# LVDS.net
KiCad netlist of a schematic drawn in Altium Designer
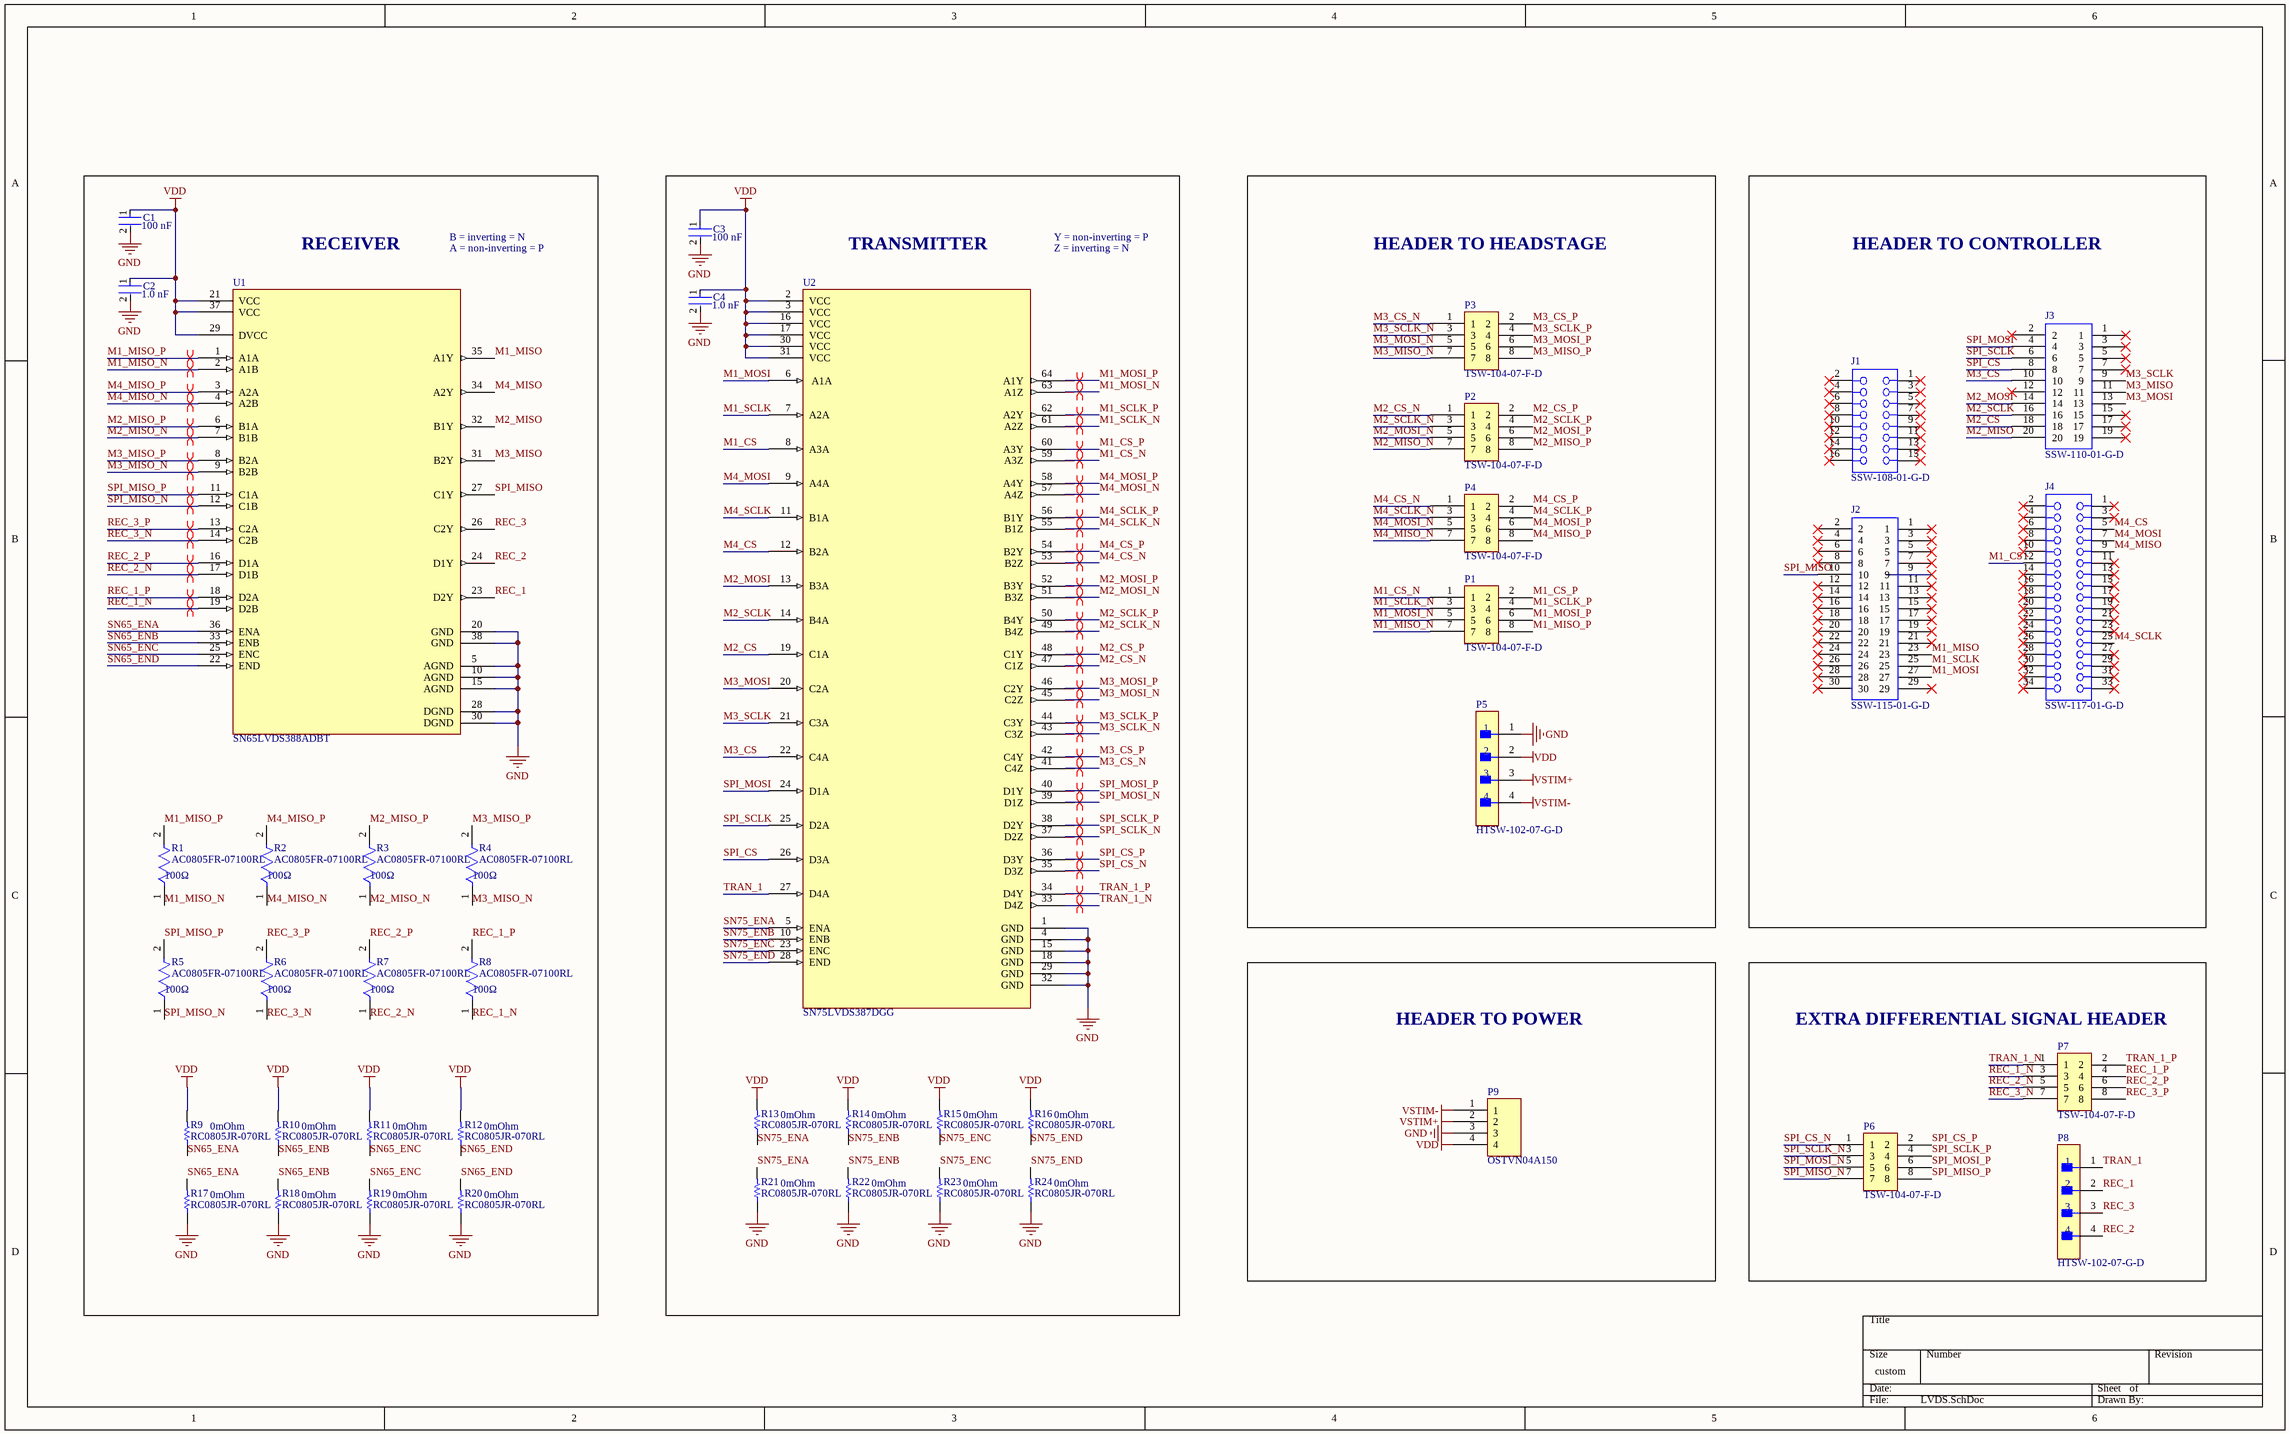
[diagram p0: LVDS.SchDoc]

(export (version "E")
  (design (tool "Eeschema 10.0.6"))
  (components
    (comp (ref "C1")
      (value "CC0805MRX7R9BB104")
      (footprint "FP-CC0805-0_85-MFG")
      (description "CAP CER 0.1UF 50V X7R 0805")
      (fields
        (field (name "TOLERANCE") "0.2")
        (field (name "OCTOPART") "https://octopart.com/cc0805mrx7r9bb104-yageo-30261726")
        (field (name "CAPACITANCE") "100 nF")
      )
      (libsource (lib "Altium Content Vault") (part "11868f565c42a9108669ba33697ecf6"))
    )
    (comp (ref "C2")
      (value "CC0805KRX7R9BB102")
      (footprint "FP-CC0805-0_85-MFG")
      (description "CAP CER 1000PF 50V X7R 0805")
      (fields
        (field (name "MANUFACTURER") "Yageo")
        (field (name "OCTOPART") "https://octopart.com/cc0805krx7r9bb102-yageo-39467744")
        (field (name "CAPACITANCE") "1.0 nF")
      )
      (libsource (lib "Altium Content Vault") (part "11868f565c42a9108669ba33697ecf6"))
    )
    (comp (ref "C3")
      (value "CC0805MRX7R9BB104")
      (footprint "FP-CC0805-0_85-MFG")
      (description "CAP CER 0.1UF 50V X7R 0805")
      (fields
        (field (name "TOLERANCE") "0.2")
        (field (name "OCTOPART") "https://octopart.com/cc0805mrx7r9bb104-yageo-30261726")
        (field (name "CAPACITANCE") "100 nF")
      )
      (libsource (lib "Altium Content Vault") (part "11868f565c42a9108669ba33697ecf6"))
    )
    (comp (ref "C4")
      (value "CC0805KRX7R9BB102")
      (footprint "FP-CC0805-0_85-MFG")
      (description "CAP CER 1000PF 50V X7R 0805")
      (fields
        (field (name "MANUFACTURER") "Yageo")
        (field (name "OCTOPART") "https://octopart.com/cc0805krx7r9bb102-yageo-39467744")
        (field (name "CAPACITANCE") "1.0 nF")
      )
      (libsource (lib "Altium Content Vault") (part "11868f565c42a9108669ba33697ecf6"))
    )
    (comp (ref "J1")
      (value "SSW-108-01-G-D")
      (footprint "SMTC-SSW-108-01-X-D")
      (description "SQ Post Socket, Through-hole, Vertical, -55 to 125 degC, 2.54mm Pitch, 16-Pin, Female, RoHS")
      (fields (field (name "MANUFACTURER") "Samtec"))
      (libsource (lib "Altium Content Vault") (part "SMTC-SSW-108-X-X-D-X"))
    )
    (comp (ref "J2")
      (value "SSW-115-01-G-D")
      (footprint "SAMTEC_SSW-115-01-G-D")
      (fields (field (name "MANUFACTURER") "Samtec"))
      (libsource (lib "LVDS") (part "SSW-115-01-G-D"))
    )
    (comp (ref "J3")
      (value "SSW-110-01-G-D")
      (footprint "SAMTEC_SSW-110-01-G-D")
      (fields (field (name "MANUFACTURER") "Samtec"))
      (libsource (lib "LVDS") (part "SSW-110-01-G-D"))
    )
    (comp (ref "J4")
      (value "SSW-117-01-G-D")
      (footprint "SMTC-SSW-117-01-X-D")
      (description "SQ Post Socket, Through-hole, Vertical, -55 to 125 degC, 2.54 mm Pitch, 34-Pin, Female, RoHS")
      (fields (field (name "MANUFACTURER") "Samtec"))
      (libsource (lib "Altium Content Vault") (part "SMTC-SSW-117-01-X-D"))
    )
    (comp (ref "P1")
      (value "TSW-104-07-F-D")
      (footprint "SAMTEC_TSW-104-07-F-D")
      (fields (field (name "MANUFACTURER") "Samtec"))
      (libsource (lib "LVDS") (part "TSW-104-07-F-D"))
    )
    (comp (ref "P2")
      (value "TSW-104-07-F-D")
      (footprint "SAMTEC_TSW-104-07-F-D")
      (fields (field (name "MANUFACTURER") "Samtec"))
      (libsource (lib "LVDS") (part "TSW-104-07-F-D"))
    )
    (comp (ref "P3")
      (value "TSW-104-07-F-D")
      (footprint "SAMTEC_TSW-104-07-F-D")
      (fields (field (name "MANUFACTURER") "Samtec"))
      (libsource (lib "LVDS") (part "TSW-104-07-F-D"))
    )
    (comp (ref "P4")
      (value "TSW-104-07-F-D")
      (footprint "SAMTEC_TSW-104-07-F-D")
      (fields (field (name "MANUFACTURER") "Samtec"))
      (libsource (lib "LVDS") (part "TSW-104-07-F-D"))
    )
    (comp (ref "P5")
      (value "HTSW-102-07-G-D")
      (footprint "FP-HTSW-102-07-G-D-MFG")
      (description "CONN HEADER VERT 4POS 2.54MM")
      (fields
        (field (name "MANUFACTURER") "Samtec")
        (field (name "OCTOPART") "https://octopart.com/htsw-102-07-g-d-samtec-10531767")
      )
      (libsource (lib "Altium Content Vault") (part "299a8cea1bdcbc3624fe62c390fa72c"))
    )
    (comp (ref "P6")
      (value "TSW-104-07-F-D")
      (footprint "SAMTEC_TSW-104-07-F-D")
      (fields (field (name "MANUFACTURER") "Samtec"))
      (libsource (lib "LVDS") (part "TSW-104-07-F-D"))
    )
    (comp (ref "P7")
      (value "TSW-104-07-F-D")
      (footprint "SAMTEC_TSW-104-07-F-D")
      (fields (field (name "MANUFACTURER") "Samtec"))
      (libsource (lib "LVDS") (part "TSW-104-07-F-D"))
    )
    (comp (ref "P8")
      (value "HTSW-102-07-G-D")
      (footprint "FP-HTSW-102-07-G-D-MFG")
      (description "CONN HEADER VERT 4POS 2.54MM")
      (fields
        (field (name "MANUFACTURER") "Samtec")
        (field (name "OCTOPART") "https://octopart.com/htsw-102-07-g-d-samtec-10531767")
      )
      (libsource (lib "Altium Content Vault") (part "299a8cea1bdcbc3624fe62c390fa72c"))
    )
    (comp (ref "P9")
      (value "OSTVN04A150")
      (footprint "OSTVN04A150")
      (description "Barrier Strip Terminal Block, 6A, 1 Row(s), 1 Deck(s)")
      (fields (field (name "MANUFACTURER") "On-Shore Technology") (field (name "SAFETY APPROVAL") "UL,CUL"))
      (libsource (lib "LVDS") (part "OSTVN04A150"))
    )
    (comp (ref "R1")
      (value "AC0805FR-07100RL")
      (footprint "FP-AC0805-MFG")
      (description "Res Thick Film 0805 100 Ohm 1% 1/8W ±100ppm/°C Molded SMD Paper T/R")
      (fields
        (field (name "TOLERANCE") "0.01")
        (field (name "OCTOPART") "https://octopart.com/ac0805fr-07100rl-yageo-24517276")
        (field (name "RESISTANCE") "100Ω")
      )
      (libsource (lib "Altium Content Vault") (part "1029c3af85768c4190bb7ad29bc67b5"))
    )
    (comp (ref "R2")
      (value "AC0805FR-07100RL")
      (footprint "FP-AC0805-MFG")
      (description "Res Thick Film 0805 100 Ohm 1% 1/8W ±100ppm/°C Molded SMD Paper T/R")
      (fields
        (field (name "TOLERANCE") "0.01")
        (field (name "OCTOPART") "https://octopart.com/ac0805fr-07100rl-yageo-24517276")
        (field (name "RESISTANCE") "100Ω")
      )
      (libsource (lib "Altium Content Vault") (part "1029c3af85768c4190bb7ad29bc67b5"))
    )
    (comp (ref "R3")
      (value "AC0805FR-07100RL")
      (footprint "FP-AC0805-MFG")
      (description "Res Thick Film 0805 100 Ohm 1% 1/8W ±100ppm/°C Molded SMD Paper T/R")
      (fields
        (field (name "TOLERANCE") "0.01")
        (field (name "OCTOPART") "https://octopart.com/ac0805fr-07100rl-yageo-24517276")
        (field (name "RESISTANCE") "100Ω")
      )
      (libsource (lib "Altium Content Vault") (part "1029c3af85768c4190bb7ad29bc67b5"))
    )
    (comp (ref "R4")
      (value "AC0805FR-07100RL")
      (footprint "FP-AC0805-MFG")
      (description "Res Thick Film 0805 100 Ohm 1% 1/8W ±100ppm/°C Molded SMD Paper T/R")
      (fields
        (field (name "TOLERANCE") "0.01")
        (field (name "OCTOPART") "https://octopart.com/ac0805fr-07100rl-yageo-24517276")
        (field (name "RESISTANCE") "100Ω")
      )
      (libsource (lib "Altium Content Vault") (part "1029c3af85768c4190bb7ad29bc67b5"))
    )
    (comp (ref "R5")
      (value "AC0805FR-07100RL")
      (footprint "FP-AC0805-MFG")
      (description "Res Thick Film 0805 100 Ohm 1% 1/8W ±100ppm/°C Molded SMD Paper T/R")
      (fields
        (field (name "TOLERANCE") "0.01")
        (field (name "OCTOPART") "https://octopart.com/ac0805fr-07100rl-yageo-24517276")
        (field (name "RESISTANCE") "100Ω")
      )
      (libsource (lib "Altium Content Vault") (part "1029c3af85768c4190bb7ad29bc67b5"))
    )
    (comp (ref "R6")
      (value "AC0805FR-07100RL")
      (footprint "FP-AC0805-MFG")
      (description "Res Thick Film 0805 100 Ohm 1% 1/8W ±100ppm/°C Molded SMD Paper T/R")
      (fields
        (field (name "TOLERANCE") "0.01")
        (field (name "OCTOPART") "https://octopart.com/ac0805fr-07100rl-yageo-24517276")
        (field (name "RESISTANCE") "100Ω")
      )
      (libsource (lib "Altium Content Vault") (part "1029c3af85768c4190bb7ad29bc67b5"))
    )
    (comp (ref "R7")
      (value "AC0805FR-07100RL")
      (footprint "FP-AC0805-MFG")
      (description "Res Thick Film 0805 100 Ohm 1% 1/8W ±100ppm/°C Molded SMD Paper T/R")
      (fields
        (field (name "TOLERANCE") "0.01")
        (field (name "OCTOPART") "https://octopart.com/ac0805fr-07100rl-yageo-24517276")
        (field (name "RESISTANCE") "100Ω")
      )
      (libsource (lib "Altium Content Vault") (part "1029c3af85768c4190bb7ad29bc67b5"))
    )
    (comp (ref "R8")
      (value "AC0805FR-07100RL")
      (footprint "FP-AC0805-MFG")
      (description "Res Thick Film 0805 100 Ohm 1% 1/8W ±100ppm/°C Molded SMD Paper T/R")
      (fields
        (field (name "TOLERANCE") "0.01")
        (field (name "OCTOPART") "https://octopart.com/ac0805fr-07100rl-yageo-24517276")
        (field (name "RESISTANCE") "100Ω")
      )
      (libsource (lib "Altium Content Vault") (part "1029c3af85768c4190bb7ad29bc67b5"))
    )
    (comp (ref "R9")
      (value "RC0805JR-070RL")
      (footprint "RESC2013X60X35ML10T20")
      (fields
        (field (name "RESISTANCE") "0mOhm")
        (field (name "TOLERANCE") "5%")
        (field (name "MANUFACTURER") "Yageo")
      )
      (libsource (lib "Altium Content Vault") (part "RES-2"))
    )
    (comp (ref "R10")
      (value "RC0805JR-070RL")
      (footprint "RESC2013X60X35ML10T20")
      (fields
        (field (name "RESISTANCE") "0mOhm")
        (field (name "TOLERANCE") "5%")
        (field (name "MANUFACTURER") "Yageo")
      )
      (libsource (lib "Altium Content Vault") (part "RES-2"))
    )
    (comp (ref "R11")
      (value "RC0805JR-070RL")
      (footprint "RESC2013X60X35ML10T20")
      (fields
        (field (name "RESISTANCE") "0mOhm")
        (field (name "TOLERANCE") "5%")
        (field (name "MANUFACTURER") "Yageo")
      )
      (libsource (lib "Altium Content Vault") (part "RES-2"))
    )
    (comp (ref "R12")
      (value "RC0805JR-070RL")
      (footprint "RESC2013X60X35ML10T20")
      (fields
        (field (name "RESISTANCE") "0mOhm")
        (field (name "TOLERANCE") "5%")
        (field (name "MANUFACTURER") "Yageo")
      )
      (libsource (lib "Altium Content Vault") (part "RES-2"))
    )
    (comp (ref "R13")
      (value "RC0805JR-070RL")
      (footprint "RESC2013X60X35ML10T20")
      (fields
        (field (name "RESISTANCE") "0mOhm")
        (field (name "TOLERANCE") "5%")
        (field (name "MANUFACTURER") "Yageo")
      )
      (libsource (lib "Altium Content Vault") (part "RES-2"))
    )
    (comp (ref "R14")
      (value "RC0805JR-070RL")
      (footprint "RESC2013X60X35ML10T20")
      (fields
        (field (name "RESISTANCE") "0mOhm")
        (field (name "TOLERANCE") "5%")
        (field (name "MANUFACTURER") "Yageo")
      )
      (libsource (lib "Altium Content Vault") (part "RES-2"))
    )
    (comp (ref "R15")
      (value "RC0805JR-070RL")
      (footprint "RESC2013X60X35ML10T20")
      (fields
        (field (name "RESISTANCE") "0mOhm")
        (field (name "TOLERANCE") "5%")
        (field (name "MANUFACTURER") "Yageo")
      )
      (libsource (lib "Altium Content Vault") (part "RES-2"))
    )
    (comp (ref "R16")
      (value "RC0805JR-070RL")
      (footprint "RESC2013X60X35ML10T20")
      (fields
        (field (name "RESISTANCE") "0mOhm")
        (field (name "TOLERANCE") "5%")
        (field (name "MANUFACTURER") "Yageo")
      )
      (libsource (lib "Altium Content Vault") (part "RES-2"))
    )
    (comp (ref "R17")
      (value "RC0805JR-070RL")
      (footprint "RESC2013X60X35ML10T20")
      (fields
        (field (name "RESISTANCE") "0mOhm")
        (field (name "TOLERANCE") "5%")
        (field (name "MANUFACTURER") "Yageo")
      )
      (libsource (lib "Altium Content Vault") (part "RES-2"))
    )
    (comp (ref "R18")
      (value "RC0805JR-070RL")
      (footprint "RESC2013X60X35ML10T20")
      (fields
        (field (name "RESISTANCE") "0mOhm")
        (field (name "TOLERANCE") "5%")
        (field (name "MANUFACTURER") "Yageo")
      )
      (libsource (lib "Altium Content Vault") (part "RES-2"))
    )
    (comp (ref "R19")
      (value "RC0805JR-070RL")
      (footprint "RESC2013X60X35ML10T20")
      (fields
        (field (name "RESISTANCE") "0mOhm")
        (field (name "TOLERANCE") "5%")
        (field (name "MANUFACTURER") "Yageo")
      )
      (libsource (lib "Altium Content Vault") (part "RES-2"))
    )
    (comp (ref "R20")
      (value "RC0805JR-070RL")
      (footprint "RESC2013X60X35ML10T20")
      (fields
        (field (name "RESISTANCE") "0mOhm")
        (field (name "TOLERANCE") "5%")
        (field (name "MANUFACTURER") "Yageo")
      )
      (libsource (lib "Altium Content Vault") (part "RES-2"))
    )
    (comp (ref "R21")
      (value "RC0805JR-070RL")
      (footprint "RESC2013X60X35ML10T20")
      (fields
        (field (name "RESISTANCE") "0mOhm")
        (field (name "TOLERANCE") "5%")
        (field (name "MANUFACTURER") "Yageo")
      )
      (libsource (lib "Altium Content Vault") (part "RES-2"))
    )
    (comp (ref "R22")
      (value "RC0805JR-070RL")
      (footprint "RESC2013X60X35ML10T20")
      (fields
        (field (name "RESISTANCE") "0mOhm")
        (field (name "TOLERANCE") "5%")
        (field (name "MANUFACTURER") "Yageo")
      )
      (libsource (lib "Altium Content Vault") (part "RES-2"))
    )
    (comp (ref "R23")
      (value "RC0805JR-070RL")
      (footprint "RESC2013X60X35ML10T20")
      (fields
        (field (name "RESISTANCE") "0mOhm")
        (field (name "TOLERANCE") "5%")
        (field (name "MANUFACTURER") "Yageo")
      )
      (libsource (lib "Altium Content Vault") (part "RES-2"))
    )
    (comp (ref "R24")
      (value "RC0805JR-070RL")
      (footprint "RESC2013X60X35ML10T20")
      (fields
        (field (name "RESISTANCE") "0mOhm")
        (field (name "TOLERANCE") "5%")
        (field (name "MANUFACTURER") "Yageo")
      )
      (libsource (lib "Altium Content Vault") (part "RES-2"))
    )
    (comp (ref "U1")
      (value "SN65LVDS388ADBT")
      (footprint "DBT0038A_N")
      (description "Line Receiver, 8 Func, 8 Rcvr, CMOS, PDSO38")
      (fields (field (name "MANUFACTURER") "Texas Instruments"))
      (libsource (lib "LVDS") (part "SN65LVDS388ADBT"))
    )
    (comp (ref "U2")
      (value "SN75LVDS387DGG")
      (footprint "DGG64")
      (description "Line Driver, 16 Func, 16 Driver, CMOS, PDSO64")
      (fields (field (name "MANUFACTURER") "Texas Instruments"))
      (libsource (lib "LVDS") (part "SN75LVDS387DGG"))
    )
  )
  (nets
    (net (code "1") (name "/M1_CS") (class "Default")
      (node (ref "J4") (pin "12") (pinfunction "12_12") (pintype "passive"))
      (node (ref "U2") (pin "8") (pinfunction "A3A_8") (pintype "input"))
    )
    (net (code "2") (name "/M1_CS_N") (class "Default")
      (node (ref "P1") (pin "1") (pinfunction "1_1") (pintype "passive"))
      (node (ref "U2") (pin "59") (pinfunction "A3Z_59") (pintype "output"))
    )
    (net (code "3") (name "/M1_CS_P") (class "Default")
      (node (ref "P1") (pin "2") (pinfunction "2_2") (pintype "passive"))
      (node (ref "U2") (pin "60") (pinfunction "A3Y_60") (pintype "output"))
    )
    (net (code "4") (name "/M1_MISO") (class "Default")
      (node (ref "J2") (pin "23") (pinfunction "23_23") (pintype "passive"))
      (node (ref "U1") (pin "35") (pinfunction "A1Y_35") (pintype "output"))
    )
    (net (code "5") (name "/M1_MISO_N") (class "Default")
      (node (ref "P1") (pin "7") (pinfunction "7_7") (pintype "passive"))
      (node (ref "R1") (pin "1") (pinfunction "1_1") (pintype "passive"))
      (node (ref "U1") (pin "2") (pinfunction "A1B_2") (pintype "input"))
    )
    (net (code "6") (name "/M1_MISO_P") (class "Default")
      (node (ref "P1") (pin "8") (pinfunction "8_8") (pintype "passive"))
      (node (ref "R1") (pin "2") (pinfunction "2_2") (pintype "passive"))
      (node (ref "U1") (pin "1") (pinfunction "A1A_1") (pintype "input"))
    )
    (net (code "7") (name "/M1_MOSI") (class "Default")
      (node (ref "J2") (pin "27") (pinfunction "27_27") (pintype "passive"))
      (node (ref "U2") (pin "6") (pinfunction "_A1A_6") (pintype "input"))
    )
    (net (code "8") (name "/M1_MOSI_N") (class "Default")
      (node (ref "P1") (pin "5") (pinfunction "5_5") (pintype "passive"))
      (node (ref "U2") (pin "63") (pinfunction "A1Z_63") (pintype "output"))
    )
    (net (code "9") (name "/M1_MOSI_P") (class "Default")
      (node (ref "P1") (pin "6") (pinfunction "6_6") (pintype "passive"))
      (node (ref "U2") (pin "64") (pinfunction "A1Y_64") (pintype "output"))
    )
    (net (code "10") (name "/M1_SCLK") (class "Default")
      (node (ref "J2") (pin "25") (pinfunction "25_25") (pintype "passive"))
      (node (ref "U2") (pin "7") (pinfunction "A2A_7") (pintype "input"))
    )
    (net (code "11") (name "/M1_SCLK_N") (class "Default")
      (node (ref "P1") (pin "3") (pinfunction "3_3") (pintype "passive"))
      (node (ref "U2") (pin "61") (pinfunction "A2Z_61") (pintype "output"))
    )
    (net (code "12") (name "/M1_SCLK_P") (class "Default")
      (node (ref "P1") (pin "4") (pinfunction "4_4") (pintype "passive"))
      (node (ref "U2") (pin "62") (pinfunction "A2Y_62") (pintype "output"))
    )
    (net (code "13") (name "/M2_CS") (class "Default")
      (node (ref "J3") (pin "18") (pinfunction "18_18") (pintype "passive"))
      (node (ref "U2") (pin "19") (pinfunction "C1A_19") (pintype "input"))
    )
    (net (code "14") (name "/M2_CS_N") (class "Default")
      (node (ref "P2") (pin "1") (pinfunction "1_1") (pintype "passive"))
      (node (ref "U2") (pin "47") (pinfunction "C1Z_47") (pintype "output"))
    )
    (net (code "15") (name "/M2_CS_P") (class "Default")
      (node (ref "P2") (pin "2") (pinfunction "2_2") (pintype "passive"))
      (node (ref "U2") (pin "48") (pinfunction "C1Y_48") (pintype "output"))
    )
    (net (code "16") (name "/M2_MISO") (class "Default")
      (node (ref "J3") (pin "20") (pinfunction "20_20") (pintype "passive"))
      (node (ref "U1") (pin "32") (pinfunction "B1Y_32") (pintype "output"))
    )
    (net (code "17") (name "/M2_MISO_N") (class "Default")
      (node (ref "P2") (pin "7") (pinfunction "7_7") (pintype "passive"))
      (node (ref "R3") (pin "1") (pinfunction "1_1") (pintype "passive"))
      (node (ref "U1") (pin "7") (pinfunction "B1B_7") (pintype "input"))
    )
    (net (code "18") (name "/M2_MISO_P") (class "Default")
      (node (ref "P2") (pin "8") (pinfunction "8_8") (pintype "passive"))
      (node (ref "R3") (pin "2") (pinfunction "2_2") (pintype "passive"))
      (node (ref "U1") (pin "6") (pinfunction "B1A_6") (pintype "input"))
    )
    (net (code "19") (name "/M2_MOSI") (class "Default")
      (node (ref "J3") (pin "14") (pinfunction "14_14") (pintype "passive"))
      (node (ref "U2") (pin "13") (pinfunction "B3A_13") (pintype "input"))
    )
    (net (code "20") (name "/M2_MOSI_N") (class "Default")
      (node (ref "P2") (pin "5") (pinfunction "5_5") (pintype "passive"))
      (node (ref "U2") (pin "51") (pinfunction "B3Z_51") (pintype "output"))
    )
    (net (code "21") (name "/M2_MOSI_P") (class "Default")
      (node (ref "P2") (pin "6") (pinfunction "6_6") (pintype "passive"))
      (node (ref "U2") (pin "52") (pinfunction "B3Y_52") (pintype "output"))
    )
    (net (code "22") (name "/M2_SCLK") (class "Default")
      (node (ref "J3") (pin "16") (pinfunction "16_16") (pintype "passive"))
      (node (ref "U2") (pin "14") (pinfunction "B4A_14") (pintype "input"))
    )
    (net (code "23") (name "/M2_SCLK_N") (class "Default")
      (node (ref "P2") (pin "3") (pinfunction "3_3") (pintype "passive"))
      (node (ref "U2") (pin "49") (pinfunction "B4Z_49") (pintype "output"))
    )
    (net (code "24") (name "/M2_SCLK_P") (class "Default")
      (node (ref "P2") (pin "4") (pinfunction "4_4") (pintype "passive"))
      (node (ref "U2") (pin "50") (pinfunction "B4Y_50") (pintype "output"))
    )
    (net (code "25") (name "/M3_CS") (class "Default")
      (node (ref "J3") (pin "10") (pinfunction "10_10") (pintype "passive"))
      (node (ref "U2") (pin "22") (pinfunction "C4A_22") (pintype "input"))
    )
    (net (code "26") (name "/M3_CS_N") (class "Default")
      (node (ref "P3") (pin "1") (pinfunction "1_1") (pintype "passive"))
      (node (ref "U2") (pin "41") (pinfunction "C4Z_41") (pintype "output"))
    )
    (net (code "27") (name "/M3_CS_P") (class "Default")
      (node (ref "P3") (pin "2") (pinfunction "2_2") (pintype "passive"))
      (node (ref "U2") (pin "42") (pinfunction "C4Y_42") (pintype "output"))
    )
    (net (code "28") (name "/M3_MISO") (class "Default")
      (node (ref "J3") (pin "11") (pinfunction "11_11") (pintype "passive"))
      (node (ref "U1") (pin "31") (pinfunction "B2Y_31") (pintype "output"))
    )
    (net (code "29") (name "/M3_MISO_N") (class "Default")
      (node (ref "P3") (pin "7") (pinfunction "7_7") (pintype "passive"))
      (node (ref "R4") (pin "1") (pinfunction "1_1") (pintype "passive"))
      (node (ref "U1") (pin "9") (pinfunction "B2B_9") (pintype "input"))
    )
    (net (code "30") (name "/M3_MISO_P") (class "Default")
      (node (ref "P3") (pin "8") (pinfunction "8_8") (pintype "passive"))
      (node (ref "R4") (pin "2") (pinfunction "2_2") (pintype "passive"))
      (node (ref "U1") (pin "8") (pinfunction "B2A_8") (pintype "input"))
    )
    (net (code "31") (name "/M3_MOSI") (class "Default")
      (node (ref "J3") (pin "13") (pinfunction "13_13") (pintype "passive"))
      (node (ref "U2") (pin "20") (pinfunction "C2A_20") (pintype "input"))
    )
    (net (code "32") (name "/M3_MOSI_N") (class "Default")
      (node (ref "P3") (pin "5") (pinfunction "5_5") (pintype "passive"))
      (node (ref "U2") (pin "45") (pinfunction "C2Z_45") (pintype "output"))
    )
    (net (code "33") (name "/M3_MOSI_P") (class "Default")
      (node (ref "P3") (pin "6") (pinfunction "6_6") (pintype "passive"))
      (node (ref "U2") (pin "46") (pinfunction "C2Y_46") (pintype "output"))
    )
    (net (code "34") (name "/M3_SCLK") (class "Default")
      (node (ref "J3") (pin "9") (pinfunction "9_9") (pintype "passive"))
      (node (ref "U2") (pin "21") (pinfunction "C3A_21") (pintype "input"))
    )
    (net (code "35") (name "/M3_SCLK_N") (class "Default")
      (node (ref "P3") (pin "3") (pinfunction "3_3") (pintype "passive"))
      (node (ref "U2") (pin "43") (pinfunction "C3Z_43") (pintype "output"))
    )
    (net (code "36") (name "/M3_SCLK_P") (class "Default")
      (node (ref "P3") (pin "4") (pinfunction "4_4") (pintype "passive"))
      (node (ref "U2") (pin "44") (pinfunction "C3Y_44") (pintype "output"))
    )
    (net (code "37") (name "/M4_CS") (class "Default")
      (node (ref "J4") (pin "5") (pinfunction "5_5") (pintype "passive"))
      (node (ref "U2") (pin "12") (pinfunction "B2A_12") (pintype "input"))
    )
    (net (code "38") (name "/M4_CS_N") (class "Default")
      (node (ref "P4") (pin "1") (pinfunction "1_1") (pintype "passive"))
      (node (ref "U2") (pin "53") (pinfunction "B2Z_53") (pintype "output"))
    )
    (net (code "39") (name "/M4_CS_P") (class "Default")
      (node (ref "P4") (pin "2") (pinfunction "2_2") (pintype "passive"))
      (node (ref "U2") (pin "54") (pinfunction "B2Y_54") (pintype "output"))
    )
    (net (code "40") (name "/M4_MISO") (class "Default")
      (node (ref "J4") (pin "9") (pinfunction "9_9") (pintype "passive"))
      (node (ref "U1") (pin "34") (pinfunction "A2Y_34") (pintype "output"))
    )
    (net (code "41") (name "/M4_MISO_N") (class "Default")
      (node (ref "P4") (pin "7") (pinfunction "7_7") (pintype "passive"))
      (node (ref "R2") (pin "1") (pinfunction "1_1") (pintype "passive"))
      (node (ref "U1") (pin "4") (pinfunction "A2B_4") (pintype "input"))
    )
    (net (code "42") (name "/M4_MISO_P") (class "Default")
      (node (ref "P4") (pin "8") (pinfunction "8_8") (pintype "passive"))
      (node (ref "R2") (pin "2") (pinfunction "2_2") (pintype "passive"))
      (node (ref "U1") (pin "3") (pinfunction "A2A_3") (pintype "input"))
    )
    (net (code "43") (name "/M4_MOSI") (class "Default")
      (node (ref "J4") (pin "7") (pinfunction "7_7") (pintype "passive"))
      (node (ref "U2") (pin "9") (pinfunction "A4A_9") (pintype "input"))
    )
    (net (code "44") (name "/M4_MOSI_N") (class "Default")
      (node (ref "P4") (pin "5") (pinfunction "5_5") (pintype "passive"))
      (node (ref "U2") (pin "57") (pinfunction "A4Z_57") (pintype "output"))
    )
    (net (code "45") (name "/M4_MOSI_P") (class "Default")
      (node (ref "P4") (pin "6") (pinfunction "6_6") (pintype "passive"))
      (node (ref "U2") (pin "58") (pinfunction "A4Y_58") (pintype "output"))
    )
    (net (code "46") (name "/M4_SCLK") (class "Default")
      (node (ref "J4") (pin "25") (pinfunction "25_25") (pintype "passive"))
      (node (ref "U2") (pin "11") (pinfunction "B1A_11") (pintype "input"))
    )
    (net (code "47") (name "/M4_SCLK_N") (class "Default")
      (node (ref "P4") (pin "3") (pinfunction "3_3") (pintype "passive"))
      (node (ref "U2") (pin "55") (pinfunction "B1Z_55") (pintype "output"))
    )
    (net (code "48") (name "/M4_SCLK_P") (class "Default")
      (node (ref "P4") (pin "4") (pinfunction "4_4") (pintype "passive"))
      (node (ref "U2") (pin "56") (pinfunction "B1Y_56") (pintype "output"))
    )
    (net (code "49") (name "/REC_1") (class "Default")
      (node (ref "P8") (pin "2") (pinfunction "2_2") (pintype "passive"))
      (node (ref "U1") (pin "23") (pinfunction "D2Y_23") (pintype "output"))
    )
    (net (code "50") (name "/REC_1_N") (class "Default")
      (node (ref "P7") (pin "3") (pinfunction "3_3") (pintype "passive"))
      (node (ref "R8") (pin "1") (pinfunction "1_1") (pintype "passive"))
      (node (ref "U1") (pin "19") (pinfunction "D2B_19") (pintype "input"))
    )
    (net (code "51") (name "/REC_1_P") (class "Default")
      (node (ref "P7") (pin "4") (pinfunction "4_4") (pintype "passive"))
      (node (ref "R8") (pin "2") (pinfunction "2_2") (pintype "passive"))
      (node (ref "U1") (pin "18") (pinfunction "D2A_18") (pintype "input"))
    )
    (net (code "52") (name "/REC_2") (class "Default")
      (node (ref "P8") (pin "4") (pinfunction "4_4") (pintype "passive"))
      (node (ref "U1") (pin "24") (pinfunction "D1Y_24") (pintype "output"))
    )
    (net (code "53") (name "/REC_2_N") (class "Default")
      (node (ref "P7") (pin "5") (pinfunction "5_5") (pintype "passive"))
      (node (ref "R7") (pin "1") (pinfunction "1_1") (pintype "passive"))
      (node (ref "U1") (pin "17") (pinfunction "D1B_17") (pintype "input"))
    )
    (net (code "54") (name "/REC_2_P") (class "Default")
      (node (ref "P7") (pin "6") (pinfunction "6_6") (pintype "passive"))
      (node (ref "R7") (pin "2") (pinfunction "2_2") (pintype "passive"))
      (node (ref "U1") (pin "16") (pinfunction "D1A_16") (pintype "input"))
    )
    (net (code "55") (name "/REC_3") (class "Default")
      (node (ref "P8") (pin "3") (pinfunction "3_3") (pintype "passive"))
      (node (ref "U1") (pin "26") (pinfunction "C2Y_26") (pintype "output"))
    )
    (net (code "56") (name "/REC_3_N") (class "Default")
      (node (ref "P7") (pin "7") (pinfunction "7_7") (pintype "passive"))
      (node (ref "R6") (pin "1") (pinfunction "1_1") (pintype "passive"))
      (node (ref "U1") (pin "14") (pinfunction "C2B_14") (pintype "input"))
    )
    (net (code "57") (name "/REC_3_P") (class "Default")
      (node (ref "P7") (pin "8") (pinfunction "8_8") (pintype "passive"))
      (node (ref "R6") (pin "2") (pinfunction "2_2") (pintype "passive"))
      (node (ref "U1") (pin "13") (pinfunction "C2A_13") (pintype "input"))
    )
    (net (code "58") (name "/SN65_ENA") (class "Default")
      (node (ref "R17") (pin "2") (pinfunction "2_2") (pintype "passive"))
      (node (ref "R9") (pin "1") (pinfunction "1_1") (pintype "passive"))
      (node (ref "U1") (pin "36") (pinfunction "ENA_36") (pintype "input"))
    )
    (net (code "59") (name "/SN65_ENB") (class "Default")
      (node (ref "R10") (pin "1") (pinfunction "1_1") (pintype "passive"))
      (node (ref "R18") (pin "2") (pinfunction "2_2") (pintype "passive"))
      (node (ref "U1") (pin "33") (pinfunction "ENB_33") (pintype "input"))
    )
    (net (code "60") (name "/SN65_ENC") (class "Default")
      (node (ref "R11") (pin "1") (pinfunction "1_1") (pintype "passive"))
      (node (ref "R19") (pin "2") (pinfunction "2_2") (pintype "passive"))
      (node (ref "U1") (pin "25") (pinfunction "ENC_25") (pintype "input"))
    )
    (net (code "61") (name "/SN65_END") (class "Default")
      (node (ref "R12") (pin "1") (pinfunction "1_1") (pintype "passive"))
      (node (ref "R20") (pin "2") (pinfunction "2_2") (pintype "passive"))
      (node (ref "U1") (pin "22") (pinfunction "END_22") (pintype "input"))
    )
    (net (code "62") (name "/SN75_ENA") (class "Default")
      (node (ref "R13") (pin "1") (pinfunction "1_1") (pintype "passive"))
      (node (ref "R21") (pin "2") (pinfunction "2_2") (pintype "passive"))
      (node (ref "U2") (pin "5") (pinfunction "ENA_5") (pintype "input"))
    )
    (net (code "63") (name "/SN75_ENB") (class "Default")
      (node (ref "R14") (pin "1") (pinfunction "1_1") (pintype "passive"))
      (node (ref "R22") (pin "2") (pinfunction "2_2") (pintype "passive"))
      (node (ref "U2") (pin "10") (pinfunction "ENB_10") (pintype "input"))
    )
    (net (code "64") (name "/SN75_ENC") (class "Default")
      (node (ref "R15") (pin "1") (pinfunction "1_1") (pintype "passive"))
      (node (ref "R23") (pin "2") (pinfunction "2_2") (pintype "passive"))
      (node (ref "U2") (pin "23") (pinfunction "ENC_23") (pintype "input"))
    )
    (net (code "65") (name "/SN75_END") (class "Default")
      (node (ref "R16") (pin "1") (pinfunction "1_1") (pintype "passive"))
      (node (ref "R24") (pin "2") (pinfunction "2_2") (pintype "passive"))
      (node (ref "U2") (pin "28") (pinfunction "END_28") (pintype "input"))
    )
    (net (code "66") (name "/SPI_CS") (class "Default")
      (node (ref "J3") (pin "8") (pinfunction "8_8") (pintype "passive"))
      (node (ref "U2") (pin "26") (pinfunction "D3A_26") (pintype "input"))
    )
    (net (code "67") (name "/SPI_CS_N") (class "Default")
      (node (ref "P6") (pin "1") (pinfunction "1_1") (pintype "passive"))
      (node (ref "U2") (pin "35") (pinfunction "D3Z_35") (pintype "output"))
    )
    (net (code "68") (name "/SPI_CS_P") (class "Default")
      (node (ref "P6") (pin "2") (pinfunction "2_2") (pintype "passive"))
      (node (ref "U2") (pin "36") (pinfunction "D3Y_36") (pintype "output"))
    )
    (net (code "69") (name "/SPI_MISO") (class "Default")
      (node (ref "J2") (pin "10") (pinfunction "10_10") (pintype "passive"))
      (node (ref "U1") (pin "27") (pinfunction "C1Y_27") (pintype "output"))
    )
    (net (code "70") (name "/SPI_MISO_N") (class "Default")
      (node (ref "P6") (pin "7") (pinfunction "7_7") (pintype "passive"))
      (node (ref "R5") (pin "1") (pinfunction "1_1") (pintype "passive"))
      (node (ref "U1") (pin "12") (pinfunction "C1B_12") (pintype "input"))
    )
    (net (code "71") (name "/SPI_MISO_P") (class "Default")
      (node (ref "P6") (pin "8") (pinfunction "8_8") (pintype "passive"))
      (node (ref "R5") (pin "2") (pinfunction "2_2") (pintype "passive"))
      (node (ref "U1") (pin "11") (pinfunction "C1A_11") (pintype "input"))
    )
    (net (code "72") (name "/SPI_MOSI") (class "Default")
      (node (ref "J3") (pin "4") (pinfunction "4_4") (pintype "passive"))
      (node (ref "U2") (pin "24") (pinfunction "D1A_24") (pintype "input"))
    )
    (net (code "73") (name "/SPI_MOSI_N") (class "Default")
      (node (ref "P6") (pin "5") (pinfunction "5_5") (pintype "passive"))
      (node (ref "U2") (pin "39") (pinfunction "D1Z_39") (pintype "output"))
    )
    (net (code "74") (name "/SPI_MOSI_P") (class "Default")
      (node (ref "P6") (pin "6") (pinfunction "6_6") (pintype "passive"))
      (node (ref "U2") (pin "40") (pinfunction "D1Y_40") (pintype "output"))
    )
    (net (code "75") (name "/SPI_SCLK") (class "Default")
      (node (ref "J3") (pin "6") (pinfunction "6_6") (pintype "passive"))
      (node (ref "U2") (pin "25") (pinfunction "D2A_25") (pintype "input"))
    )
    (net (code "76") (name "/SPI_SCLK_N") (class "Default")
      (node (ref "P6") (pin "3") (pinfunction "3_3") (pintype "passive"))
      (node (ref "U2") (pin "37") (pinfunction "D2Z_37") (pintype "output"))
    )
    (net (code "77") (name "/SPI_SCLK_P") (class "Default")
      (node (ref "P6") (pin "4") (pinfunction "4_4") (pintype "passive"))
      (node (ref "U2") (pin "38") (pinfunction "D2Y_38") (pintype "output"))
    )
    (net (code "78") (name "/TRAN_1") (class "Default")
      (node (ref "P8") (pin "1") (pinfunction "1_1") (pintype "passive"))
      (node (ref "U2") (pin "27") (pinfunction "D4A_27") (pintype "input"))
    )
    (net (code "79") (name "/TRAN_1_N") (class "Default")
      (node (ref "P7") (pin "1") (pinfunction "1_1") (pintype "passive"))
      (node (ref "U2") (pin "33") (pinfunction "D4Z_33") (pintype "output"))
    )
    (net (code "80") (name "/TRAN_1_P") (class "Default")
      (node (ref "P7") (pin "2") (pinfunction "2_2") (pintype "passive"))
      (node (ref "U2") (pin "34") (pinfunction "D4Y_34") (pintype "output"))
    )
    (net (code "81") (name "GND") (class "Default")
      (node (ref "C1") (pin "2") (pinfunction "2_2") (pintype "passive"))
      (node (ref "C2") (pin "2") (pinfunction "2_2") (pintype "passive"))
      (node (ref "C3") (pin "2") (pinfunction "2_2") (pintype "passive"))
      (node (ref "C4") (pin "2") (pinfunction "2_2") (pintype "passive"))
      (node (ref "P5") (pin "1") (pinfunction "1_1") (pintype "passive"))
      (node (ref "P9") (pin "3") (pinfunction "3_3") (pintype "passive"))
      (node (ref "R17") (pin "1") (pinfunction "1_1") (pintype "passive"))
      (node (ref "R18") (pin "1") (pinfunction "1_1") (pintype "passive"))
      (node (ref "R19") (pin "1") (pinfunction "1_1") (pintype "passive"))
      (node (ref "R20") (pin "1") (pinfunction "1_1") (pintype "passive"))
      (node (ref "R21") (pin "1") (pinfunction "1_1") (pintype "passive"))
      (node (ref "R22") (pin "1") (pinfunction "1_1") (pintype "passive"))
      (node (ref "R23") (pin "1") (pinfunction "1_1") (pintype "passive"))
      (node (ref "R24") (pin "1") (pinfunction "1_1") (pintype "passive"))
      (node (ref "U1") (pin "10") (pinfunction "AGND_10") (pintype "power_in"))
      (node (ref "U1") (pin "15") (pinfunction "AGND_15") (pintype "power_in"))
      (node (ref "U1") (pin "20") (pinfunction "GND_20") (pintype "power_in"))
      (node (ref "U1") (pin "28") (pinfunction "DGND_28") (pintype "power_in"))
      (node (ref "U1") (pin "30") (pinfunction "DGND_30") (pintype "power_in"))
      (node (ref "U1") (pin "38") (pinfunction "GND_38") (pintype "power_in"))
      (node (ref "U1") (pin "5") (pinfunction "AGND_5") (pintype "power_in"))
      (node (ref "U2") (pin "1") (pinfunction "GND_1") (pintype "power_in"))
      (node (ref "U2") (pin "15") (pinfunction "GND_15") (pintype "power_in"))
      (node (ref "U2") (pin "18") (pinfunction "GND_18") (pintype "power_in"))
      (node (ref "U2") (pin "29") (pinfunction "GND_29") (pintype "power_in"))
      (node (ref "U2") (pin "32") (pinfunction "GND_32") (pintype "power_in"))
      (node (ref "U2") (pin "4") (pinfunction "GND_4") (pintype "power_in"))
    )
    (net (code "82") (name "VDD") (class "Default")
      (node (ref "C1") (pin "1") (pinfunction "1_1") (pintype "passive"))
      (node (ref "C2") (pin "1") (pinfunction "1_1") (pintype "passive"))
      (node (ref "C3") (pin "1") (pinfunction "1_1") (pintype "passive"))
      (node (ref "C4") (pin "1") (pinfunction "1_1") (pintype "passive"))
      (node (ref "P5") (pin "2") (pinfunction "2_2") (pintype "passive"))
      (node (ref "P9") (pin "4") (pinfunction "4_4") (pintype "passive"))
      (node (ref "R10") (pin "2") (pinfunction "2_2") (pintype "passive"))
      (node (ref "R11") (pin "2") (pinfunction "2_2") (pintype "passive"))
      (node (ref "R12") (pin "2") (pinfunction "2_2") (pintype "passive"))
      (node (ref "R13") (pin "2") (pinfunction "2_2") (pintype "passive"))
      (node (ref "R14") (pin "2") (pinfunction "2_2") (pintype "passive"))
      (node (ref "R15") (pin "2") (pinfunction "2_2") (pintype "passive"))
      (node (ref "R16") (pin "2") (pinfunction "2_2") (pintype "passive"))
      (node (ref "R9") (pin "2") (pinfunction "2_2") (pintype "passive"))
      (node (ref "U1") (pin "21") (pinfunction "VCC_21") (pintype "power_in"))
      (node (ref "U1") (pin "29") (pinfunction "DVCC_29") (pintype "power_in"))
      (node (ref "U1") (pin "37") (pinfunction "VCC_37") (pintype "power_in"))
      (node (ref "U2") (pin "16") (pinfunction "VCC_16") (pintype "power_in"))
      (node (ref "U2") (pin "17") (pinfunction "VCC_17") (pintype "power_in"))
      (node (ref "U2") (pin "2") (pinfunction "VCC_2") (pintype "power_in"))
      (node (ref "U2") (pin "3") (pinfunction "VCC_3") (pintype "power_in"))
      (node (ref "U2") (pin "30") (pinfunction "VCC_30") (pintype "power_in"))
      (node (ref "U2") (pin "31") (pinfunction "VCC_31") (pintype "power_in"))
    )
    (net (code "83") (name "VSTIM+") (class "Default")
      (node (ref "P5") (pin "3") (pinfunction "3_3") (pintype "passive"))
      (node (ref "P9") (pin "2") (pinfunction "2_2") (pintype "passive"))
    )
    (net (code "84") (name "VSTIM-") (class "Default")
      (node (ref "P5") (pin "4") (pinfunction "4_4") (pintype "passive"))
      (node (ref "P9") (pin "1") (pinfunction "1_1") (pintype "passive"))
    )
    (net (code "85") (name "unconnected-(J1-Pad1)") (class "Default")
      (node (ref "J1") (pin "1") (pinfunction "1_1") (pintype "passive+no_connect"))
    )
    (net (code "86") (name "unconnected-(J1-Pad2)") (class "Default")
      (node (ref "J1") (pin "2") (pinfunction "2_2") (pintype "passive+no_connect"))
    )
    (net (code "87") (name "unconnected-(J1-Pad3)") (class "Default")
      (node (ref "J1") (pin "3") (pinfunction "3_3") (pintype "passive+no_connect"))
    )
    (net (code "88") (name "unconnected-(J1-Pad4)") (class "Default")
      (node (ref "J1") (pin "4") (pinfunction "4_4") (pintype "passive+no_connect"))
    )
    (net (code "89") (name "unconnected-(J1-Pad5)") (class "Default")
      (node (ref "J1") (pin "5") (pinfunction "5_5") (pintype "passive+no_connect"))
    )
    (net (code "90") (name "unconnected-(J1-Pad6)") (class "Default")
      (node (ref "J1") (pin "6") (pinfunction "6_6") (pintype "passive+no_connect"))
    )
    (net (code "91") (name "unconnected-(J1-Pad7)") (class "Default")
      (node (ref "J1") (pin "7") (pinfunction "7_7") (pintype "passive+no_connect"))
    )
    (net (code "92") (name "unconnected-(J1-Pad8)") (class "Default")
      (node (ref "J1") (pin "8") (pinfunction "8_8") (pintype "passive+no_connect"))
    )
    (net (code "93") (name "unconnected-(J1-Pad9)") (class "Default")
      (node (ref "J1") (pin "9") (pinfunction "9_9") (pintype "passive+no_connect"))
    )
    (net (code "94") (name "unconnected-(J1-Pad10)") (class "Default")
      (node (ref "J1") (pin "10") (pinfunction "10_10") (pintype "passive+no_connect"))
    )
    (net (code "95") (name "unconnected-(J1-Pad11)") (class "Default")
      (node (ref "J1") (pin "11") (pinfunction "11_11") (pintype "passive+no_connect"))
    )
    (net (code "96") (name "unconnected-(J1-Pad12)") (class "Default")
      (node (ref "J1") (pin "12") (pinfunction "12_12") (pintype "passive+no_connect"))
    )
    (net (code "97") (name "unconnected-(J1-Pad13)") (class "Default")
      (node (ref "J1") (pin "13") (pinfunction "13_13") (pintype "passive+no_connect"))
    )
    (net (code "98") (name "unconnected-(J1-Pad14)") (class "Default")
      (node (ref "J1") (pin "14") (pinfunction "14_14") (pintype "passive+no_connect"))
    )
    (net (code "99") (name "unconnected-(J1-Pad15)") (class "Default")
      (node (ref "J1") (pin "15") (pinfunction "15_15") (pintype "passive+no_connect"))
    )
    (net (code "100") (name "unconnected-(J1-Pad16)") (class "Default")
      (node (ref "J1") (pin "16") (pinfunction "16_16") (pintype "passive+no_connect"))
    )
    (net (code "101") (name "unconnected-(J2-Pad1)") (class "Default")
      (node (ref "J2") (pin "1") (pinfunction "1_1") (pintype "passive+no_connect"))
    )
    (net (code "102") (name "unconnected-(J2-Pad2)") (class "Default")
      (node (ref "J2") (pin "2") (pinfunction "2_2") (pintype "passive+no_connect"))
    )
    (net (code "103") (name "unconnected-(J2-Pad3)") (class "Default")
      (node (ref "J2") (pin "3") (pinfunction "3_3") (pintype "passive+no_connect"))
    )
    (net (code "104") (name "unconnected-(J2-Pad4)") (class "Default")
      (node (ref "J2") (pin "4") (pinfunction "4_4") (pintype "passive+no_connect"))
    )
    (net (code "105") (name "unconnected-(J2-Pad5)") (class "Default")
      (node (ref "J2") (pin "5") (pinfunction "5_5") (pintype "passive+no_connect"))
    )
    (net (code "106") (name "unconnected-(J2-Pad6)") (class "Default")
      (node (ref "J2") (pin "6") (pinfunction "6_6") (pintype "passive+no_connect"))
    )
    (net (code "107") (name "unconnected-(J2-Pad7)") (class "Default")
      (node (ref "J2") (pin "7") (pinfunction "7_7") (pintype "passive+no_connect"))
    )
    (net (code "108") (name "unconnected-(J2-Pad8)") (class "Default")
      (node (ref "J2") (pin "8") (pinfunction "8_8") (pintype "passive+no_connect"))
    )
    (net (code "109") (name "unconnected-(J2-Pad9)") (class "Default")
      (node (ref "J2") (pin "9") (pinfunction "9_9") (pintype "passive+no_connect"))
    )
    (net (code "110") (name "unconnected-(J2-Pad11)") (class "Default")
      (node (ref "J2") (pin "11") (pinfunction "11_11") (pintype "passive+no_connect"))
    )
    (net (code "111") (name "unconnected-(J2-Pad12)") (class "Default")
      (node (ref "J2") (pin "12") (pinfunction "12_12") (pintype "passive+no_connect"))
    )
    (net (code "112") (name "unconnected-(J2-Pad13)") (class "Default")
      (node (ref "J2") (pin "13") (pinfunction "13_13") (pintype "passive+no_connect"))
    )
    (net (code "113") (name "unconnected-(J2-Pad14)") (class "Default")
      (node (ref "J2") (pin "14") (pinfunction "14_14") (pintype "passive+no_connect"))
    )
    (net (code "114") (name "unconnected-(J2-Pad15)") (class "Default")
      (node (ref "J2") (pin "15") (pinfunction "15_15") (pintype "passive+no_connect"))
    )
    (net (code "115") (name "unconnected-(J2-Pad16)") (class "Default")
      (node (ref "J2") (pin "16") (pinfunction "16_16") (pintype "passive+no_connect"))
    )
    (net (code "116") (name "unconnected-(J2-Pad17)") (class "Default")
      (node (ref "J2") (pin "17") (pinfunction "17_17") (pintype "passive+no_connect"))
    )
    (net (code "117") (name "unconnected-(J2-Pad18)") (class "Default")
      (node (ref "J2") (pin "18") (pinfunction "18_18") (pintype "passive+no_connect"))
    )
    (net (code "118") (name "unconnected-(J2-Pad19)") (class "Default")
      (node (ref "J2") (pin "19") (pinfunction "19_19") (pintype "passive+no_connect"))
    )
    (net (code "119") (name "unconnected-(J2-Pad20)") (class "Default")
      (node (ref "J2") (pin "20") (pinfunction "20_20") (pintype "passive+no_connect"))
    )
    (net (code "120") (name "unconnected-(J2-Pad21)") (class "Default")
      (node (ref "J2") (pin "21") (pinfunction "21_21") (pintype "passive+no_connect"))
    )
    (net (code "121") (name "unconnected-(J2-Pad22)") (class "Default")
      (node (ref "J2") (pin "22") (pinfunction "22_22") (pintype "passive+no_connect"))
    )
    (net (code "122") (name "unconnected-(J2-Pad24)") (class "Default")
      (node (ref "J2") (pin "24") (pinfunction "24_24") (pintype "passive+no_connect"))
    )
    (net (code "123") (name "unconnected-(J2-Pad26)") (class "Default")
      (node (ref "J2") (pin "26") (pinfunction "26_26") (pintype "passive+no_connect"))
    )
    (net (code "124") (name "unconnected-(J2-Pad28)") (class "Default")
      (node (ref "J2") (pin "28") (pinfunction "28_28") (pintype "passive+no_connect"))
    )
    (net (code "125") (name "unconnected-(J2-Pad29)") (class "Default")
      (node (ref "J2") (pin "29") (pinfunction "29_29") (pintype "passive+no_connect"))
    )
    (net (code "126") (name "unconnected-(J2-Pad30)") (class "Default")
      (node (ref "J2") (pin "30") (pinfunction "30_30") (pintype "passive+no_connect"))
    )
    (net (code "127") (name "unconnected-(J3-Pad1)") (class "Default")
      (node (ref "J3") (pin "1") (pinfunction "1_1") (pintype "passive+no_connect"))
    )
    (net (code "128") (name "unconnected-(J3-Pad2)") (class "Default")
      (node (ref "J3") (pin "2") (pinfunction "2_2") (pintype "passive+no_connect"))
    )
    (net (code "129") (name "unconnected-(J3-Pad3)") (class "Default")
      (node (ref "J3") (pin "3") (pinfunction "3_3") (pintype "passive+no_connect"))
    )
    (net (code "130") (name "unconnected-(J3-Pad5)") (class "Default")
      (node (ref "J3") (pin "5") (pinfunction "5_5") (pintype "passive+no_connect"))
    )
    (net (code "131") (name "unconnected-(J3-Pad7)") (class "Default")
      (node (ref "J3") (pin "7") (pinfunction "7_7") (pintype "passive+no_connect"))
    )
    (net (code "132") (name "unconnected-(J3-Pad12)") (class "Default")
      (node (ref "J3") (pin "12") (pinfunction "12_12") (pintype "passive+no_connect"))
    )
    (net (code "133") (name "unconnected-(J3-Pad15)") (class "Default")
      (node (ref "J3") (pin "15") (pinfunction "15_15") (pintype "passive+no_connect"))
    )
    (net (code "134") (name "unconnected-(J3-Pad17)") (class "Default")
      (node (ref "J3") (pin "17") (pinfunction "17_17") (pintype "passive+no_connect"))
    )
    (net (code "135") (name "unconnected-(J3-Pad19)") (class "Default")
      (node (ref "J3") (pin "19") (pinfunction "19_19") (pintype "passive+no_connect"))
    )
    (net (code "136") (name "unconnected-(J4-Pad1)") (class "Default")
      (node (ref "J4") (pin "1") (pinfunction "1_1") (pintype "passive+no_connect"))
    )
    (net (code "137") (name "unconnected-(J4-Pad2)") (class "Default")
      (node (ref "J4") (pin "2") (pinfunction "2_2") (pintype "passive+no_connect"))
    )
    (net (code "138") (name "unconnected-(J4-Pad3)") (class "Default")
      (node (ref "J4") (pin "3") (pinfunction "3_3") (pintype "passive+no_connect"))
    )
    (net (code "139") (name "unconnected-(J4-Pad4)") (class "Default")
      (node (ref "J4") (pin "4") (pinfunction "4_4") (pintype "passive+no_connect"))
    )
    (net (code "140") (name "unconnected-(J4-Pad6)") (class "Default")
      (node (ref "J4") (pin "6") (pinfunction "6_6") (pintype "passive+no_connect"))
    )
    (net (code "141") (name "unconnected-(J4-Pad8)") (class "Default")
      (node (ref "J4") (pin "8") (pinfunction "8_8") (pintype "passive+no_connect"))
    )
    (net (code "142") (name "unconnected-(J4-Pad10)") (class "Default")
      (node (ref "J4") (pin "10") (pinfunction "10_10") (pintype "passive+no_connect"))
    )
    (net (code "143") (name "unconnected-(J4-Pad11)") (class "Default")
      (node (ref "J4") (pin "11") (pinfunction "11_11") (pintype "passive+no_connect"))
    )
    (net (code "144") (name "unconnected-(J4-Pad13)") (class "Default")
      (node (ref "J4") (pin "13") (pinfunction "13_13") (pintype "passive+no_connect"))
    )
    (net (code "145") (name "unconnected-(J4-Pad14)") (class "Default")
      (node (ref "J4") (pin "14") (pinfunction "14_14") (pintype "passive+no_connect"))
    )
    (net (code "146") (name "unconnected-(J4-Pad15)") (class "Default")
      (node (ref "J4") (pin "15") (pinfunction "15_15") (pintype "passive+no_connect"))
    )
    (net (code "147") (name "unconnected-(J4-Pad16)") (class "Default")
      (node (ref "J4") (pin "16") (pinfunction "16_16") (pintype "passive+no_connect"))
    )
    (net (code "148") (name "unconnected-(J4-Pad17)") (class "Default")
      (node (ref "J4") (pin "17") (pinfunction "17_17") (pintype "passive+no_connect"))
    )
    (net (code "149") (name "unconnected-(J4-Pad18)") (class "Default")
      (node (ref "J4") (pin "18") (pinfunction "18_18") (pintype "passive+no_connect"))
    )
    (net (code "150") (name "unconnected-(J4-Pad19)") (class "Default")
      (node (ref "J4") (pin "19") (pinfunction "19_19") (pintype "passive+no_connect"))
    )
    (net (code "151") (name "unconnected-(J4-Pad20)") (class "Default")
      (node (ref "J4") (pin "20") (pinfunction "20_20") (pintype "passive+no_connect"))
    )
    (net (code "152") (name "unconnected-(J4-Pad21)") (class "Default")
      (node (ref "J4") (pin "21") (pinfunction "21_21") (pintype "passive+no_connect"))
    )
    (net (code "153") (name "unconnected-(J4-Pad22)") (class "Default")
      (node (ref "J4") (pin "22") (pinfunction "22_22") (pintype "passive+no_connect"))
    )
    (net (code "154") (name "unconnected-(J4-Pad23)") (class "Default")
      (node (ref "J4") (pin "23") (pinfunction "23_23") (pintype "passive+no_connect"))
    )
    (net (code "155") (name "unconnected-(J4-Pad24)") (class "Default")
      (node (ref "J4") (pin "24") (pinfunction "24_24") (pintype "passive+no_connect"))
    )
    (net (code "156") (name "unconnected-(J4-Pad26)") (class "Default")
      (node (ref "J4") (pin "26") (pinfunction "26_26") (pintype "passive+no_connect"))
    )
    (net (code "157") (name "unconnected-(J4-Pad27)") (class "Default")
      (node (ref "J4") (pin "27") (pinfunction "27_27") (pintype "passive+no_connect"))
    )
    (net (code "158") (name "unconnected-(J4-Pad28)") (class "Default")
      (node (ref "J4") (pin "28") (pinfunction "28_28") (pintype "passive+no_connect"))
    )
    (net (code "159") (name "unconnected-(J4-Pad29)") (class "Default")
      (node (ref "J4") (pin "29") (pinfunction "29_29") (pintype "passive+no_connect"))
    )
    (net (code "160") (name "unconnected-(J4-Pad30)") (class "Default")
      (node (ref "J4") (pin "30") (pinfunction "30_30") (pintype "passive+no_connect"))
    )
    (net (code "161") (name "unconnected-(J4-Pad31)") (class "Default")
      (node (ref "J4") (pin "31") (pinfunction "31_31") (pintype "passive+no_connect"))
    )
    (net (code "162") (name "unconnected-(J4-Pad32)") (class "Default")
      (node (ref "J4") (pin "32") (pinfunction "32_32") (pintype "passive+no_connect"))
    )
    (net (code "163") (name "unconnected-(J4-Pad33)") (class "Default")
      (node (ref "J4") (pin "33") (pinfunction "33_33") (pintype "passive+no_connect"))
    )
    (net (code "164") (name "unconnected-(J4-Pad34)") (class "Default")
      (node (ref "J4") (pin "34") (pinfunction "34_34") (pintype "passive+no_connect"))
    )
  )
)
